# Analog_RPM_Schematic.net
KiCad netlist of a schematic drawn in Altium Designer
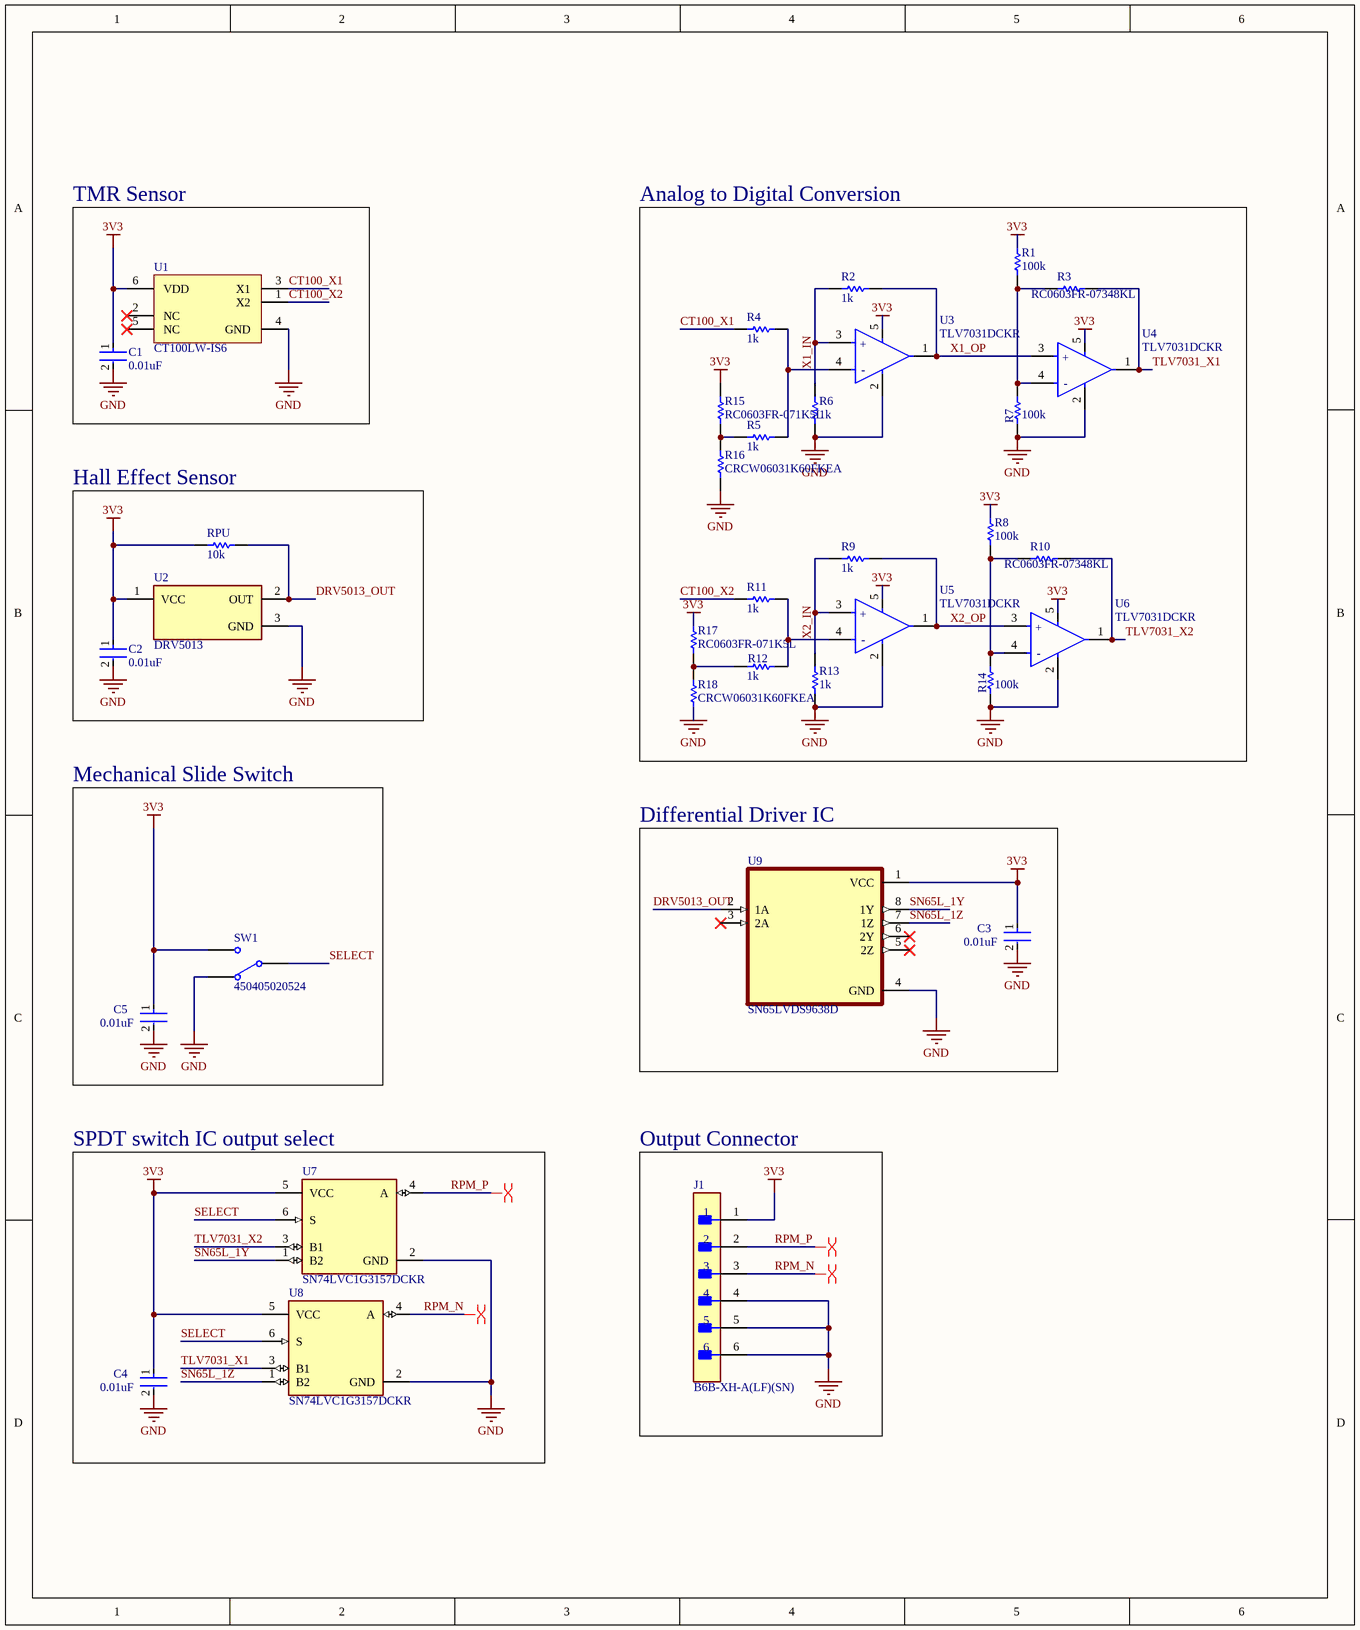
[diagram p0: Analog RPM Schematic.SchDoc]

(export (version "E")
  (design (tool "Eeschema 10.0.6"))
  (components
    (comp (ref "C1")
      (value "0.01uF")
      (footprint "FP-GRM188-0_1-e0_2_0_55-IPC_A")
      (description "Chip Multilayer Ceramic Capacitors for General Purpose, 0603, 10uF, X5R, 15%, 20%, 6.3V")
      (fields (field (name "VOLTAGE") "6.3V") (field (name "TOLERANCE") "20%"))
      (libsource (lib "Altium Content Vault") (part "02cd4be3c70576c341d710602a673aa"))
    )
    (comp (ref "C2")
      (value "0.01uF")
      (footprint "FP-GRM188-0_1-e0_2_0_55-IPC_A")
      (description "Chip Multilayer Ceramic Capacitors for General Purpose, 0603, 10uF, X5R, 15%, 20%, 6.3V")
      (fields (field (name "VOLTAGE") "6.3V") (field (name "TOLERANCE") "20%"))
      (libsource (lib "Altium Content Vault") (part "02cd4be3c70576c341d710602a673aa"))
    )
    (comp (ref "C3")
      (value "0.01uF")
      (footprint "FP-GRM188-0_1-e0_2_0_55-IPC_A")
      (description "Chip Multilayer Ceramic Capacitors for General Purpose, 0603, 10uF, X5R, 15%, 20%, 6.3V")
      (fields (field (name "VOLTAGE") "6.3V") (field (name "TOLERANCE") "20%"))
      (libsource (lib "Altium Content Vault") (part "02cd4be3c70576c341d710602a673aa"))
    )
    (comp (ref "C4")
      (value "0.01uF")
      (footprint "FP-GRM188-0_1-e0_2_0_55-IPC_A")
      (description "Chip Multilayer Ceramic Capacitors for General Purpose, 0603, 10uF, X5R, 15%, 20%, 6.3V")
      (fields (field (name "VOLTAGE") "6.3V") (field (name "TOLERANCE") "20%"))
      (libsource (lib "Altium Content Vault") (part "02cd4be3c70576c341d710602a673aa"))
    )
    (comp (ref "C5")
      (value "0.01uF")
      (footprint "FP-GRM188-0_1-e0_2_0_55-IPC_A")
      (description "Chip Multilayer Ceramic Capacitors for General Purpose, 0603, 10uF, X5R, 15%, 20%, 6.3V")
      (fields (field (name "VOLTAGE") "6.3V") (field (name "TOLERANCE") "20%"))
      (libsource (lib "Altium Content Vault") (part "02cd4be3c70576c341d710602a673aa"))
    )
    (comp (ref "J1")
      (value "B6B-XH-A(LF)(SN)")
      (footprint "FP-B6B-XH-A_LF_SN-MFG")
      (description "CONN HEADER VERT 6POS 2.5MM")
      (libsource (lib "Altium Content Vault") (part "f2cb566baf1c37ab5a3b8e90bbeafd6"))
    )
    (comp (ref "R1")
      (value "100k")
      (footprint "RESC2013X70X40NL20T20")
      (fields
        (field (name "TOLERANCE") "5%")
        (field (name "POWER") "125mW")
        (field (name "Comment") "Resistor 100K +/-5% 0805 125 mW")
      )
      (libsource (lib "SUBC") (part "RES"))
    )
    (comp (ref "R2")
      (value "1k")
      (footprint "RESC2013X70X40NL20T20")
      (fields
        (field (name "TOLERANCE") "5%")
        (field (name "POWER") "500mW")
        (field (name "Comment") "Resistor 1K +/-5% 0805 500 mW")
      )
      (libsource (lib "SUBC") (part "RES"))
    )
    (comp (ref "R3")
      (value "RC0603FR-07348KL")
      (footprint "RESC1608X55X25LL10T15")
      (fields (field (name "MANUFACTURER") "Yageo"))
      (libsource (lib "Altium Content Vault") (part "RES"))
    )
    (comp (ref "R4")
      (value "1k")
      (footprint "RESC2013X70X40NL20T20")
      (fields
        (field (name "TOLERANCE") "5%")
        (field (name "POWER") "500mW")
        (field (name "Comment") "Resistor 1K +/-5% 0805 500 mW")
      )
      (libsource (lib "SUBC") (part "RES"))
    )
    (comp (ref "R5")
      (value "1k")
      (footprint "RESC2013X70X40NL20T20")
      (fields
        (field (name "TOLERANCE") "5%")
        (field (name "POWER") "500mW")
        (field (name "Comment") "Resistor 1K +/-5% 0805 500 mW")
      )
      (libsource (lib "SUBC") (part "RES"))
    )
    (comp (ref "R6")
      (value "1k")
      (footprint "RESC2013X70X40NL20T20")
      (fields
        (field (name "TOLERANCE") "5%")
        (field (name "POWER") "500mW")
        (field (name "Comment") "Resistor 1K +/-5% 0805 500 mW")
      )
      (libsource (lib "SUBC") (part "RES"))
    )
    (comp (ref "R7")
      (value "100k")
      (footprint "RESC2013X70X40NL20T20")
      (fields
        (field (name "TOLERANCE") "5%")
        (field (name "POWER") "125mW")
        (field (name "Comment") "Resistor 100K +/-5% 0805 125 mW")
      )
      (libsource (lib "SUBC") (part "RES"))
    )
    (comp (ref "R8")
      (value "100k")
      (footprint "RESC2013X70X40NL20T20")
      (fields
        (field (name "TOLERANCE") "5%")
        (field (name "POWER") "125mW")
        (field (name "Comment") "Resistor 100K +/-5% 0805 125 mW")
      )
      (libsource (lib "SUBC") (part "RES"))
    )
    (comp (ref "R9")
      (value "1k")
      (footprint "RESC2013X70X40NL20T20")
      (fields
        (field (name "TOLERANCE") "5%")
        (field (name "POWER") "500mW")
        (field (name "Comment") "Resistor 1K +/-5% 0805 500 mW")
      )
      (libsource (lib "SUBC") (part "RES"))
    )
    (comp (ref "R10")
      (value "RC0603FR-07348KL")
      (footprint "RESC1608X55X25LL10T15")
      (fields (field (name "MANUFACTURER") "Yageo"))
      (libsource (lib "Altium Content Vault") (part "RES"))
    )
    (comp (ref "R11")
      (value "1k")
      (footprint "RESC2013X70X40NL20T20")
      (fields
        (field (name "TOLERANCE") "5%")
        (field (name "POWER") "500mW")
        (field (name "Comment") "Resistor 1K +/-5% 0805 500 mW")
      )
      (libsource (lib "SUBC") (part "RES"))
    )
    (comp (ref "R12")
      (value "1k")
      (footprint "RESC2013X70X40NL20T20")
      (fields
        (field (name "TOLERANCE") "5%")
        (field (name "POWER") "500mW")
        (field (name "Comment") "Resistor 1K +/-5% 0805 500 mW")
      )
      (libsource (lib "SUBC") (part "RES"))
    )
    (comp (ref "R13")
      (value "1k")
      (footprint "RESC2013X70X40NL20T20")
      (fields
        (field (name "TOLERANCE") "5%")
        (field (name "POWER") "500mW")
        (field (name "Comment") "Resistor 1K +/-5% 0805 500 mW")
      )
      (libsource (lib "SUBC") (part "RES"))
    )
    (comp (ref "R14")
      (value "100k")
      (footprint "RESC2013X70X40NL20T20")
      (fields
        (field (name "TOLERANCE") "5%")
        (field (name "POWER") "125mW")
        (field (name "Comment") "Resistor 100K +/-5% 0805 125 mW")
      )
      (libsource (lib "SUBC") (part "RES"))
    )
    (comp (ref "R15")
      (value "RC0603FR-071K5L")
      (footprint "RESC1608X55X25ML10T15")
      (description "Chip Resistor, 1.5 KOhm, +/- 1%, 0.1 W, -55 to 155 degC, 0603 (1608 Metric), RoHS, Tape and Reel")
      (fields (field (name "TOLERANCE") "1%") (field (name "MANUFACTURER") "Yageo"))
      (libsource (lib "Altium Content Vault") (part "RES-2"))
    )
    (comp (ref "R16")
      (value "CRCW06031K60FKEA")
      (footprint "RESC1609X50X30LL10T20")
      (fields (field (name "MANUFACTURER") "Vishay Dale"))
      (libsource (lib "Altium Content Vault") (part "RES"))
    )
    (comp (ref "R17")
      (value "RC0603FR-071K5L")
      (footprint "RESC1608X55X25ML10T15")
      (description "Chip Resistor, 1.5 KOhm, +/- 1%, 0.1 W, -55 to 155 degC, 0603 (1608 Metric), RoHS, Tape and Reel")
      (fields (field (name "TOLERANCE") "1%") (field (name "MANUFACTURER") "Yageo"))
      (libsource (lib "Altium Content Vault") (part "RES-2"))
    )
    (comp (ref "R18")
      (value "CRCW06031K60FKEA")
      (footprint "RESC1609X50X30LL10T20")
      (fields (field (name "MANUFACTURER") "Vishay Dale"))
      (libsource (lib "Altium Content Vault") (part "RES"))
    )
    (comp (ref "RPU")
      (value "10k")
      (footprint "RESC1609X50X30NL8T20")
      (description "Chip Resistor, 10 KOhm, +/- 1%, 100 mW, -55 to 155 degC, 0603 (1608 Metric), RoHS, Tape and Reel")
      (fields (field (name "MANUFACTURER") "Vishay Semiconductor"))
      (libsource (lib "Altium Content Vault") (part "RES-2"))
    )
    (comp (ref "SW1")
      (value "450405020524")
      (footprint "450405020524")
      (description "450405020524 WS-SLSU Mini Slide Switch")
      (libsource (lib "Altium Content Vault") (part "SPDT"))
    )
    (comp (ref "U1")
      (value "CT100LW-IS6")
      (footprint "SOT95P280X120-6_CT100LW-IS6_N")
      (description "Differential TMR high sensitivity Magnetic 1D Linear sensor")
      (libsource (lib "Altium Content Vault") (part "0a3280b8e41331bf3dc358578cf0801"))
    )
    (comp (ref "U2")
      (value "DRV5013")
      (footprint "FP-DBZ0003A-MFG")
      (description "SENSOR HALL ANALOG SOT23-3")
      (libsource (lib "Altium Content Vault") (part "efe7807550706e6e893497d2b9c67b4"))
    )
    (comp (ref "U3")
      (value "TLV7031DCKR")
      (footprint "FP-DCK0005A-IPC_A")
      (description "VOLTAGE COMPARATOR")
      (libsource (lib "Altium Content Vault") (part "3e335d1df146cd5910f9749ec3defb6"))
    )
    (comp (ref "U4")
      (value "TLV7031DCKR")
      (footprint "FP-DCK0005A-IPC_A")
      (description "VOLTAGE COMPARATOR")
      (libsource (lib "Altium Content Vault") (part "3e335d1df146cd5910f9749ec3defb6"))
    )
    (comp (ref "U5")
      (value "TLV7031DCKR")
      (footprint "FP-DCK0005A-IPC_A")
      (description "VOLTAGE COMPARATOR")
      (libsource (lib "Altium Content Vault") (part "3e335d1df146cd5910f9749ec3defb6"))
    )
    (comp (ref "U6")
      (value "TLV7031DCKR")
      (footprint "FP-DCK0005A-IPC_A")
      (description "VOLTAGE COMPARATOR")
      (libsource (lib "Altium Content Vault") (part "3e335d1df146cd5910f9749ec3defb6"))
    )
    (comp (ref "U7")
      (value "SN74LVC1G3157DCKR")
      (footprint "FP-DCK0006A-MFG")
      (description "SPDT, 1 Func, 1 Channel, CMOS, PDSO6")
      (libsource (lib "SUBC") (part "0261a57985ab8eeec66806cf7caee19"))
    )
    (comp (ref "U8")
      (value "SN74LVC1G3157DCKR")
      (footprint "FP-DCK0006A-MFG")
      (description "SPDT, 1 Func, 1 Channel, CMOS, PDSO6")
      (libsource (lib "SUBC") (part "0261a57985ab8eeec66806cf7caee19"))
    )
    (comp (ref "U9")
      (value "SN65LVDS9638D")
      (footprint "SOIC127P599X175-8N")
      (description "1500-Mbps LVDS dial high speed differential driver")
      (fields (field (name "MF") "Texas Instruments"))
      (libsource (lib "SUBC") (part "SN65LVDS9638D"))
    )
  )
  (nets
    (net (code "1") (name "/CT100_X1") (class "Default")
      (node (ref "R4") (pin "1") (pinfunction "1_1") (pintype "passive"))
      (node (ref "U1") (pin "3") (pinfunction "X1_3") (pintype "passive"))
    )
    (net (code "2") (name "/CT100_X2") (class "Default")
      (node (ref "R11") (pin "1") (pinfunction "1_1") (pintype "passive"))
      (node (ref "U1") (pin "1") (pinfunction "X2_1") (pintype "passive"))
    )
    (net (code "3") (name "/DRV5013_OUT") (class "Default")
      (node (ref "RPU") (pin "2") (pinfunction "2_2") (pintype "passive"))
      (node (ref "U2") (pin "2") (pinfunction "OUT_2") (pintype "passive"))
      (node (ref "U9") (pin "2") (pinfunction "1A_2") (pintype "input"))
    )
    (net (code "4") (name "/RPM_N") (class "Default")
      (node (ref "J1") (pin "3") (pinfunction "3_3") (pintype "passive"))
      (node (ref "U8") (pin "4") (pinfunction "A_4") (pintype "bidirectional"))
    )
    (net (code "5") (name "/RPM_P") (class "Default")
      (node (ref "J1") (pin "2") (pinfunction "2_2") (pintype "passive"))
      (node (ref "U7") (pin "4") (pinfunction "A_4") (pintype "bidirectional"))
    )
    (net (code "6") (name "/SELECT") (class "Default")
      (node (ref "SW1") (pin "COM") (pinfunction "COM_COM") (pintype "passive"))
      (node (ref "U7") (pin "6") (pinfunction "S_6") (pintype "input"))
      (node (ref "U8") (pin "6") (pinfunction "S_6") (pintype "input"))
    )
    (net (code "7") (name "/SN65L_1Y") (class "Default")
      (node (ref "U7") (pin "1") (pinfunction "B2_1") (pintype "bidirectional"))
      (node (ref "U9") (pin "8") (pinfunction "1Y_8") (pintype "output"))
    )
    (net (code "8") (name "/SN65L_1Z") (class "Default")
      (node (ref "U8") (pin "1") (pinfunction "B2_1") (pintype "bidirectional"))
      (node (ref "U9") (pin "7") (pinfunction "1Z_7") (pintype "output"))
    )
    (net (code "9") (name "/TLV7031_X1") (class "Default")
      (node (ref "R3") (pin "2") (pinfunction "2_2") (pintype "passive"))
      (node (ref "U4") (pin "1") (pinfunction "OUT_1") (pintype "passive"))
      (node (ref "U8") (pin "3") (pinfunction "B1_3") (pintype "bidirectional"))
    )
    (net (code "10") (name "/TLV7031_X2") (class "Default")
      (node (ref "R10") (pin "2") (pinfunction "2_2") (pintype "passive"))
      (node (ref "U6") (pin "1") (pinfunction "OUT_1") (pintype "passive"))
      (node (ref "U7") (pin "3") (pinfunction "B1_3") (pintype "bidirectional"))
    )
    (net (code "11") (name "/X1_IN") (class "Default")
      (node (ref "R2") (pin "1") (pinfunction "1_1") (pintype "passive"))
      (node (ref "R4") (pin "2") (pinfunction "2_2") (pintype "passive"))
      (node (ref "R5") (pin "2") (pinfunction "2_2") (pintype "passive"))
      (node (ref "R6") (pin "1") (pinfunction "1_1") (pintype "passive"))
      (node (ref "U3") (pin "3") (pinfunction "IN+_3") (pintype "tri_state"))
      (node (ref "U3") (pin "4") (pinfunction "IN-_4") (pintype "tri_state"))
    )
    (net (code "12") (name "/X1_OP") (class "Default")
      (node (ref "R2") (pin "2") (pinfunction "2_2") (pintype "passive"))
      (node (ref "U3") (pin "1") (pinfunction "OUT_1") (pintype "passive"))
      (node (ref "U4") (pin "3") (pinfunction "IN+_3") (pintype "tri_state"))
    )
    (net (code "13") (name "/X2_IN") (class "Default")
      (node (ref "R11") (pin "2") (pinfunction "2_2") (pintype "passive"))
      (node (ref "R12") (pin "2") (pinfunction "2_2") (pintype "passive"))
      (node (ref "R13") (pin "1") (pinfunction "1_1") (pintype "passive"))
      (node (ref "R9") (pin "1") (pinfunction "1_1") (pintype "passive"))
      (node (ref "U5") (pin "3") (pinfunction "IN+_3") (pintype "tri_state"))
      (node (ref "U5") (pin "4") (pinfunction "IN-_4") (pintype "tri_state"))
    )
    (net (code "14") (name "/X2_OP") (class "Default")
      (node (ref "R9") (pin "2") (pinfunction "2_2") (pintype "passive"))
      (node (ref "U5") (pin "1") (pinfunction "OUT_1") (pintype "passive"))
      (node (ref "U6") (pin "3") (pinfunction "IN+_3") (pintype "tri_state"))
    )
    (net (code "15") (name "3V3") (class "Default")
      (node (ref "C1") (pin "1") (pinfunction "1_1") (pintype "passive"))
      (node (ref "C2") (pin "1") (pinfunction "1_1") (pintype "passive"))
      (node (ref "C3") (pin "1") (pinfunction "1_1") (pintype "passive"))
      (node (ref "C4") (pin "1") (pinfunction "1_1") (pintype "passive"))
      (node (ref "C5") (pin "1") (pinfunction "1_1") (pintype "passive"))
      (node (ref "J1") (pin "1") (pinfunction "1_1") (pintype "passive"))
      (node (ref "R1") (pin "1") (pinfunction "1_1") (pintype "passive"))
      (node (ref "R15") (pin "2") (pinfunction "2_2") (pintype "passive"))
      (node (ref "R17") (pin "2") (pinfunction "2_2") (pintype "passive"))
      (node (ref "R8") (pin "1") (pinfunction "1_1") (pintype "passive"))
      (node (ref "RPU") (pin "1") (pinfunction "1_1") (pintype "passive"))
      (node (ref "SW1") (pin "L2") (pinfunction "L2_L2") (pintype "passive"))
      (node (ref "U1") (pin "6") (pinfunction "VDD_6") (pintype "power_in"))
      (node (ref "U2") (pin "1") (pinfunction "VCC_1") (pintype "power_in"))
      (node (ref "U3") (pin "5") (pinfunction "VCC_5") (pintype "power_in"))
      (node (ref "U4") (pin "5") (pinfunction "VCC_5") (pintype "power_in"))
      (node (ref "U5") (pin "5") (pinfunction "VCC_5") (pintype "power_in"))
      (node (ref "U6") (pin "5") (pinfunction "VCC_5") (pintype "power_in"))
      (node (ref "U7") (pin "5") (pinfunction "VCC_5") (pintype "power_in"))
      (node (ref "U8") (pin "5") (pinfunction "VCC_5") (pintype "power_in"))
      (node (ref "U9") (pin "1") (pinfunction "VCC_1") (pintype "power_in"))
    )
    (net (code "16") (name "GND") (class "Default")
      (node (ref "C1") (pin "2") (pinfunction "2_2") (pintype "passive"))
      (node (ref "C2") (pin "2") (pinfunction "2_2") (pintype "passive"))
      (node (ref "C3") (pin "2") (pinfunction "2_2") (pintype "passive"))
      (node (ref "C4") (pin "2") (pinfunction "2_2") (pintype "passive"))
      (node (ref "C5") (pin "2") (pinfunction "2_2") (pintype "passive"))
      (node (ref "J1") (pin "4") (pinfunction "4_4") (pintype "passive"))
      (node (ref "J1") (pin "5") (pinfunction "5_5") (pintype "passive"))
      (node (ref "J1") (pin "6") (pinfunction "6_6") (pintype "passive"))
      (node (ref "R13") (pin "2") (pinfunction "2_2") (pintype "passive"))
      (node (ref "R14") (pin "2") (pinfunction "2_2") (pintype "passive"))
      (node (ref "R16") (pin "1") (pinfunction "1_1") (pintype "passive"))
      (node (ref "R18") (pin "1") (pinfunction "1_1") (pintype "passive"))
      (node (ref "R6") (pin "2") (pinfunction "2_2") (pintype "passive"))
      (node (ref "R7") (pin "2") (pinfunction "2_2") (pintype "passive"))
      (node (ref "SW1") (pin "L1") (pinfunction "L1_L1") (pintype "passive"))
      (node (ref "U1") (pin "4") (pinfunction "GND_4") (pintype "power_in"))
      (node (ref "U2") (pin "3") (pinfunction "GND_3") (pintype "power_in"))
      (node (ref "U3") (pin "2") (pinfunction "VEE_2") (pintype "power_in"))
      (node (ref "U4") (pin "2") (pinfunction "VEE_2") (pintype "power_in"))
      (node (ref "U5") (pin "2") (pinfunction "VEE_2") (pintype "power_in"))
      (node (ref "U6") (pin "2") (pinfunction "VEE_2") (pintype "power_in"))
      (node (ref "U7") (pin "2") (pinfunction "GND_2") (pintype "power_in"))
      (node (ref "U8") (pin "2") (pinfunction "GND_2") (pintype "power_in"))
      (node (ref "U9") (pin "4") (pinfunction "GND_4") (pintype "power_in"))
    )
    (net (code "17") (name "Net-(R12-Pad1)") (class "Default")
      (node (ref "R12") (pin "1") (pinfunction "1_1") (pintype "passive"))
      (node (ref "R17") (pin "1") (pinfunction "1_1") (pintype "passive"))
      (node (ref "R18") (pin "2") (pinfunction "2_2") (pintype "passive"))
    )
    (net (code "18") (name "Net-(R15-Pad1)") (class "Default")
      (node (ref "R15") (pin "1") (pinfunction "1_1") (pintype "passive"))
      (node (ref "R16") (pin "2") (pinfunction "2_2") (pintype "passive"))
      (node (ref "R5") (pin "1") (pinfunction "1_1") (pintype "passive"))
    )
    (net (code "19") (name "Net-(U4-IN-)") (class "Default")
      (node (ref "R1") (pin "2") (pinfunction "2_2") (pintype "passive"))
      (node (ref "R3") (pin "1") (pinfunction "1_1") (pintype "passive"))
      (node (ref "R7") (pin "1") (pinfunction "1_1") (pintype "passive"))
      (node (ref "U4") (pin "4") (pinfunction "IN-_4") (pintype "tri_state"))
    )
    (net (code "20") (name "Net-(U6-IN-)") (class "Default")
      (node (ref "R10") (pin "1") (pinfunction "1_1") (pintype "passive"))
      (node (ref "R14") (pin "1") (pinfunction "1_1") (pintype "passive"))
      (node (ref "R8") (pin "2") (pinfunction "2_2") (pintype "passive"))
      (node (ref "U6") (pin "4") (pinfunction "IN-_4") (pintype "tri_state"))
    )
    (net (code "21") (name "unconnected-(U1-NC-Pad2)") (class "Default")
      (node (ref "U1") (pin "2") (pinfunction "NC_2") (pintype "passive+no_connect"))
    )
    (net (code "22") (name "unconnected-(U1-NC-Pad5)") (class "Default")
      (node (ref "U1") (pin "5") (pinfunction "NC_5") (pintype "passive+no_connect"))
    )
    (net (code "23") (name "unconnected-(U9-2A-Pad3)") (class "Default")
      (node (ref "U9") (pin "3") (pinfunction "2A_3") (pintype "input+no_connect"))
    )
    (net (code "24") (name "unconnected-(U9-2Y-Pad6)") (class "Default")
      (node (ref "U9") (pin "6") (pinfunction "2Y_6") (pintype "output+no_connect"))
    )
    (net (code "25") (name "unconnected-(U9-2Z-Pad5)") (class "Default")
      (node (ref "U9") (pin "5") (pinfunction "2Z_5") (pintype "output+no_connect"))
    )
  )
)
